# BSPD.net
KiCad netlist of a schematic drawn in Altium Designer
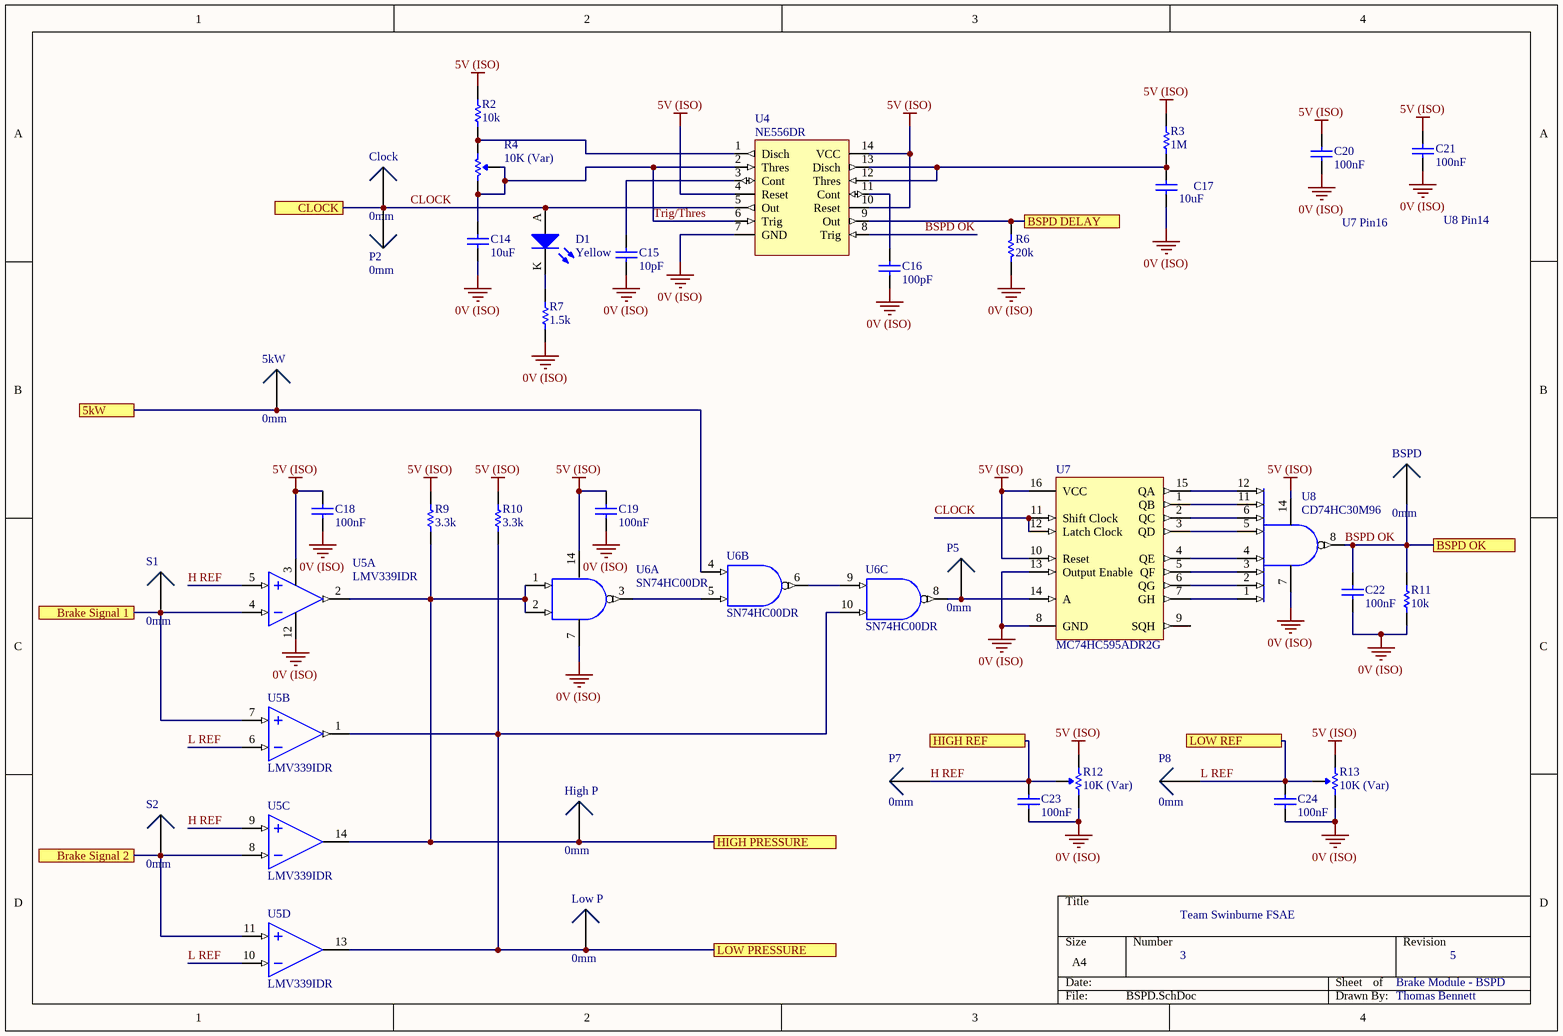
[diagram p0: BSPD.SchDoc]

(export (version "E")
  (design (tool "Eeschema 10.0.6"))
  (components
    (comp (ref "5kW")
      (value "0mm")
      (footprint "SMD Test Point")
      (fields (field (name "PART NUMBER") "SMD Test Point") (field (name "CONTACT") "NA"))
      (libsource (lib "ts_20-standard-connectors") (part "Test Point"))
    )
    (comp (ref "BSPD")
      (value "0mm")
      (footprint "SMD Test Point")
      (fields (field (name "PART NUMBER") "SMD Test Point") (field (name "CONTACT") "NA"))
      (libsource (lib "ts_20-standard-connectors") (part "Test Point"))
    )
    (comp (ref "C14")
      (value "10uF")
      (footprint "0805")
      (fields
        (field (name "PART NUMBER") "GRM21BR6YA106KE43L")
        (field (name "TOLERANCE") "10%")
        (field (name "MANUFACTURER") "muRata")
      )
      (libsource (lib "ts_20-standard-library") (part "Capacitor"))
    )
    (comp (ref "C15")
      (value "10pF")
      (footprint "0805")
      (fields
        (field (name "PART NUMBER") "GRM21A5C2E100JW01D")
        (field (name "TOLERANCE") "±5%")
        (field (name "MANUFACTURER") "muRata")
      )
      (libsource (lib "ts_20-standard-library") (part "Capacitor"))
    )
    (comp (ref "C16")
      (value "100pF")
      (footprint "0805")
      (fields
        (field (name "PART NUMBER") "GCM2165C1H101JA16D")
        (field (name "TOLERANCE") "±5%")
        (field (name "MANUFACTURER") "muRata")
      )
      (libsource (lib "ts_20-standard-library") (part "Capacitor"))
    )
    (comp (ref "C17")
      (value "10uF")
      (footprint "0805")
      (fields
        (field (name "PART NUMBER") "GRM21BR6YA106KE43L")
        (field (name "TOLERANCE") "10%")
        (field (name "MANUFACTURER") "muRata")
      )
      (libsource (lib "ts_20-standard-library") (part "Capacitor"))
    )
    (comp (ref "C18")
      (value "100nF")
      (footprint "0805")
      (fields
        (field (name "PART NUMBER") "GCM21BR71H104KA37L")
        (field (name "TOLERANCE") "±10%")
        (field (name "MANUFACTURER") "muRata")
      )
      (libsource (lib "ts_20-standard-library") (part "Capacitor"))
    )
    (comp (ref "C19")
      (value "100nF")
      (footprint "0805")
      (fields
        (field (name "PART NUMBER") "GCM21BR71E104KA37L")
        (field (name "TOLERANCE") "10%")
        (field (name "MANUFACTURER") "muRata")
      )
      (libsource (lib "ts_20-standard-library") (part "Capacitor"))
    )
    (comp (ref "C20")
      (value "100nF")
      (footprint "0805")
      (fields
        (field (name "PART NUMBER") "GCM21BR71H104KA37L")
        (field (name "TOLERANCE") "±10%")
        (field (name "MANUFACTURER") "muRata")
      )
      (libsource (lib "ts_20-standard-library") (part "Capacitor"))
    )
    (comp (ref "C21")
      (value "100nF")
      (footprint "0805")
      (fields
        (field (name "PART NUMBER") "GCM21BR71H104KA37L")
        (field (name "TOLERANCE") "±10%")
        (field (name "MANUFACTURER") "muRata")
      )
      (libsource (lib "ts_20-standard-library") (part "Capacitor"))
    )
    (comp (ref "C22")
      (value "100nF")
      (footprint "0805")
      (fields
        (field (name "PART NUMBER") "GCM21BR71H104KA37L")
        (field (name "TOLERANCE") "±10%")
        (field (name "MANUFACTURER") "muRata")
      )
      (libsource (lib "ts_20-standard-library") (part "Capacitor"))
    )
    (comp (ref "C23")
      (value "100nF")
      (footprint "0805")
      (fields
        (field (name "PART NUMBER") "GCM21BR71H104KA37L")
        (field (name "TOLERANCE") "±10%")
        (field (name "MANUFACTURER") "muRata")
      )
      (libsource (lib "ts_20-standard-library") (part "Capacitor"))
    )
    (comp (ref "C24")
      (value "100nF")
      (footprint "0805")
      (fields
        (field (name "PART NUMBER") "GCM21BR71H104KA37L")
        (field (name "TOLERANCE") "±10%")
        (field (name "MANUFACTURER") "muRata")
      )
      (libsource (lib "ts_20-standard-library") (part "Capacitor"))
    )
    (comp (ref "Clock")
      (value "0mm")
      (footprint "SMD Test Point")
      (fields (field (name "PART NUMBER") "SMD Test Point") (field (name "CONTACT") "NA"))
      (libsource (lib "ts_20-standard-connectors") (part "Test Point"))
    )
    (comp (ref "D1")
      (value "Yellow")
      (footprint "0805 LED")
      (description "Yellow LED Indication - Discrete 1.75V 0805 (2012 Metric)")
      (fields (field (name "PART NUMBER") "SML-211YTT86") (field (name "MANUFACTURER") "ROHM Semiconductor"))
      (libsource (lib "ts_20-standard-library") (part "LED"))
    )
    (comp (ref "High P")
      (value "0mm")
      (footprint "SMD Test Point")
      (fields (field (name "PART NUMBER") "SMD Test Point") (field (name "CONTACT") "NA"))
      (libsource (lib "ts_20-standard-connectors") (part "Test Point"))
    )
    (comp (ref "Low P")
      (value "0mm")
      (footprint "SMD Test Point")
      (fields (field (name "PART NUMBER") "SMD Test Point") (field (name "CONTACT") "NA"))
      (libsource (lib "ts_20-standard-connectors") (part "Test Point"))
    )
    (comp (ref "P2")
      (value "0mm")
      (footprint "TH Test Point")
      (fields (field (name "PART NUMBER") "TH Test Point") (field (name "CONTACT") "NA"))
      (libsource (lib "ts_20-standard-connectors") (part "Test Point"))
    )
    (comp (ref "P5")
      (value "0mm")
      (footprint "SMD Test Point")
      (fields (field (name "PART NUMBER") "SMD Test Point") (field (name "CONTACT") "NA"))
      (libsource (lib "ts_20-standard-connectors") (part "Test Point"))
    )
    (comp (ref "P7")
      (value "0mm")
      (footprint "TH Test Point")
      (fields (field (name "PART NUMBER") "TH Test Point") (field (name "CONTACT") "NA"))
      (libsource (lib "ts_20-standard-connectors") (part "Test Point"))
    )
    (comp (ref "P8")
      (value "0mm")
      (footprint "TH Test Point")
      (fields (field (name "PART NUMBER") "TH Test Point") (field (name "CONTACT") "NA"))
      (libsource (lib "ts_20-standard-connectors") (part "Test Point"))
    )
    (comp (ref "R2")
      (value "10k")
      (footprint "0805")
      (fields
        (field (name "PART NUMBER") "RC0805FR0710KL")
        (field (name "MANUFACTURER") "YAGEO")
        (field (name "TOLERANCE") "0.01")
      )
      (libsource (lib "ts_20-standard-library") (part "Resistor"))
    )
    (comp (ref "R3")
      (value "1M")
      (footprint "0805")
      (fields
        (field (name "PART NUMBER") "RC0805FR071ML")
        (field (name "MANUFACTURER") "YAGEO")
        (field (name "TOLERANCE") "0.01")
      )
      (libsource (lib "ts_20-standard-library") (part "Resistor"))
    )
    (comp (ref "R4")
      (value "10K (Var)")
      (footprint "B 3296")
      (fields
        (field (name "PART NUMBER") "3296W-1-103LF")
        (field (name "MANUFACTURER") "Bournes Inc")
        (field (name "TOLERANCE") "0.1")
      )
      (libsource (lib "ts_20-standard-library") (part "Resistor (Potentiometer)"))
    )
    (comp (ref "R6")
      (value "20k")
      (footprint "0805")
      (fields
        (field (name "PART NUMBER") "RC0805FR0720KL")
        (field (name "MANUFACTURER") "YAGEO")
        (field (name "TOLERANCE") "0.01")
      )
      (libsource (lib "ts_20-standard-library") (part "Resistor"))
    )
    (comp (ref "R7")
      (value "1.5k")
      (footprint "0805")
      (fields
        (field (name "PART NUMBER") "RC0805FR071K5L")
        (field (name "MANUFACTURER") "YAGEO")
        (field (name "TOLERANCE") "0.01")
      )
      (libsource (lib "ts_20-standard-library") (part "Resistor"))
    )
    (comp (ref "R9")
      (value "3.3k")
      (footprint "0805")
      (fields
        (field (name "PART NUMBER") "RC0805FR073K3L")
        (field (name "MANUFACTURER") "YAGEO")
        (field (name "TOLERANCE") "0.01")
      )
      (libsource (lib "ts_20-standard-library") (part "Resistor"))
    )
    (comp (ref "R10")
      (value "3.3k")
      (footprint "0805")
      (fields
        (field (name "PART NUMBER") "RC0805FR073K3L")
        (field (name "MANUFACTURER") "YAGEO")
        (field (name "TOLERANCE") "0.01")
      )
      (libsource (lib "ts_20-standard-library") (part "Resistor"))
    )
    (comp (ref "R11")
      (value "10k")
      (footprint "0805")
      (fields
        (field (name "PART NUMBER") "RC0805FR0710KL")
        (field (name "MANUFACTURER") "YAGEO")
        (field (name "TOLERANCE") "0.01")
      )
      (libsource (lib "ts_20-standard-library") (part "Resistor"))
    )
    (comp (ref "R12")
      (value "10K (Var)")
      (footprint "B 3296")
      (fields
        (field (name "PART NUMBER") "3296W-1-103LF")
        (field (name "MANUFACTURER") "Bournes Inc")
        (field (name "TOLERANCE") "0.1")
      )
      (libsource (lib "ts_20-standard-library") (part "Resistor (Potentiometer)"))
    )
    (comp (ref "R13")
      (value "10K (Var)")
      (footprint "B 3296")
      (fields
        (field (name "PART NUMBER") "3296W-1-103LF")
        (field (name "MANUFACTURER") "Bournes Inc")
        (field (name "TOLERANCE") "0.1")
      )
      (libsource (lib "ts_20-standard-library") (part "Resistor (Potentiometer)"))
    )
    (comp (ref "S1")
      (value "0mm")
      (footprint "TH Test Point")
      (fields (field (name "PART NUMBER") "TH Test Point") (field (name "CONTACT") "NA"))
      (libsource (lib "ts_20-standard-connectors") (part "Test Point"))
    )
    (comp (ref "S2")
      (value "0mm")
      (footprint "TH Test Point")
      (fields (field (name "PART NUMBER") "TH Test Point") (field (name "CONTACT") "NA"))
      (libsource (lib "ts_20-standard-connectors") (part "Test Point"))
    )
    (comp (ref "U4")
      (value "NE556DR")
      (footprint "14 SOIC")
      (description "IC OSC TIMER DUAL 100KHZ 14SOIC")
      (fields
        (field (name "MANUFACTURER") "Texas Instruments")
        (field (name "DIGIKEY PART NUMBER") "296-26240-1-ND")
      )
      (libsource (lib "ts_20-standard-library") (part "NE556DR"))
    )
    (comp (ref "U5")
      (value "LMV339IDR")
      (footprint "TI 14-SOIC")
      (description "Comparator General Purpose Open Collector 14-SOIC")
      (fields
        (field (name "MANUFACTURER") "Texas Instruments")
        (field (name "DIGIKEY PART NUMBER") "296-6611-2-ND")
      )
      (libsource (lib "ts_20-standard-library") (part "LMV339IDR"))
    )
    (comp (ref "U6")
      (value "SN74HC00DR")
      (footprint "TI 14-SOIC")
      (description "NAND Gate IC 4 Channel 14-SOIC")
      (fields
        (field (name "MANUFACTURER") "Texas Instruments")
        (field (name "DIGIKEY PART NUMBER") "296-1187-2-ND")
      )
      (libsource (lib "ts_20-standard-library") (part "SN74HC00DR"))
    )
    (comp (ref "U7")
      (value "MC74HC595ADR2G")
      (footprint "ON 16-SOIC")
      (description "IC SHIFT REGISTR 8BIT 3ST 16SOIC")
      (fields
        (field (name "MANUFACTURER") "ON Semiconductor")
        (field (name "DIGIKEY PART NUMBER") "MC74HC595ADR2GOSCT-ND")
      )
      (libsource (lib "ts_20-standard-library") (part "MC74HC595ADR2G"))
    )
    (comp (ref "U8")
      (value "CD74HC30M96")
      (footprint "TI 14-SOIC")
      (description "IC GATE NAND 1CH 8-INP 14SOIC")
      (fields
        (field (name "MANUFACTURER") "Texas Instruments")
        (field (name "DIGIKEY PART NUMBER") "296-14521-1-ND")
      )
      (libsource (lib "ts_20-standard-library") (part "CD74HC30M96"))
    )
  )
  (nets
    (net (code "1") (name "/5kW") (class "Default")
      (node (ref "5kW") (pin "1") (pinfunction "1_1") (pintype "passive"))
      (node (ref "U6") (pin "4") (pinfunction "2A_4") (pintype "input"))
    )
    (net (code "2") (name "/BSPD DELAY") (class "Default")
      (node (ref "R6") (pin "1") (pinfunction "1_1") (pintype "passive"))
      (node (ref "U4") (pin "9") (pinfunction "Out_9") (pintype "output"))
    )
    (net (code "3") (name "/BSPD OK") (class "Default")
      (node (ref "BSPD") (pin "1") (pinfunction "1_1") (pintype "passive"))
      (node (ref "C22") (pin "2") (pinfunction "2_2") (pintype "passive"))
      (node (ref "R11") (pin "2") (pinfunction "2_2") (pintype "passive"))
      (node (ref "U4") (pin "8") (pinfunction "Trig_8") (pintype "input"))
      (node (ref "U8") (pin "8") (pinfunction "Output_8") (pintype "output"))
    )
    (net (code "4") (name "/Brake Signal 1") (class "Default")
      (node (ref "S1") (pin "1") (pinfunction "1_1") (pintype "passive"))
      (node (ref "U5") (pin "4") (pinfunction "IN_A-_4") (pintype "input"))
      (node (ref "U5") (pin "7") (pinfunction "IN_B+_7") (pintype "input"))
    )
    (net (code "5") (name "/Brake Signal 2") (class "Default")
      (node (ref "S2") (pin "1") (pinfunction "1_1") (pintype "passive"))
      (node (ref "U5") (pin "11") (pinfunction "IN_D+_11") (pintype "input"))
      (node (ref "U5") (pin "8") (pinfunction "IN_C-_8") (pintype "input"))
    )
    (net (code "6") (name "/CLOCK") (class "Default")
      (node (ref "Clock") (pin "1") (pinfunction "1_1") (pintype "passive"))
      (node (ref "D1") (pin "A") (pinfunction "A_A") (pintype "passive"))
      (node (ref "P2") (pin "1") (pinfunction "1_1") (pintype "passive"))
      (node (ref "U4") (pin "5") (pinfunction "Out_5") (pintype "output"))
      (node (ref "U7") (pin "11") (pinfunction "Shift_Clock_11") (pintype "input"))
      (node (ref "U7") (pin "12") (pinfunction "Latch_Clock_12") (pintype "input"))
    )
    (net (code "7") (name "/H REF") (class "Default")
      (node (ref "C23") (pin "2") (pinfunction "2_2") (pintype "passive"))
      (node (ref "P7") (pin "1") (pinfunction "1_1") (pintype "passive"))
      (node (ref "R12") (pin "2") (pinfunction "Wiper_2") (pintype "passive"))
      (node (ref "U5") (pin "5") (pinfunction "IN_A+_5") (pintype "input"))
      (node (ref "U5") (pin "9") (pinfunction "IN_C+_9") (pintype "input"))
    )
    (net (code "8") (name "/HIGH PRESSURE") (class "Default")
      (node (ref "High P") (pin "1") (pinfunction "1_1") (pintype "passive"))
      (node (ref "R9") (pin "1") (pinfunction "1_1") (pintype "passive"))
      (node (ref "U5") (pin "14") (pinfunction "OUT_C_14") (pintype "passive"))
      (node (ref "U5") (pin "2") (pinfunction "OUT_A_2") (pintype "output"))
      (node (ref "U6") (pin "1") (pinfunction "1A_1") (pintype "input"))
      (node (ref "U6") (pin "2") (pinfunction "1B_2") (pintype "input"))
    )
    (net (code "9") (name "/L REF") (class "Default")
      (node (ref "C24") (pin "2") (pinfunction "2_2") (pintype "passive"))
      (node (ref "P8") (pin "1") (pinfunction "1_1") (pintype "passive"))
      (node (ref "R13") (pin "2") (pinfunction "Wiper_2") (pintype "passive"))
      (node (ref "U5") (pin "10") (pinfunction "IN_D-_10") (pintype "input"))
      (node (ref "U5") (pin "6") (pinfunction "IN_B-_6") (pintype "input"))
    )
    (net (code "10") (name "/LOW PRESSURE") (class "Default")
      (node (ref "Low P") (pin "1") (pinfunction "1_1") (pintype "passive"))
      (node (ref "R10") (pin "1") (pinfunction "1_1") (pintype "passive"))
      (node (ref "U5") (pin "1") (pinfunction "OUT_B_1") (pintype "output"))
      (node (ref "U5") (pin "13") (pinfunction "OUT_D_13") (pintype "passive"))
      (node (ref "U6") (pin "10") (pinfunction "3B_10") (pintype "input"))
    )
    (net (code "11") (name "/Trig{slash}Thres") (class "Default")
      (node (ref "C14") (pin "2") (pinfunction "2_2") (pintype "passive"))
      (node (ref "R4") (pin "1") (pinfunction "CCW_1") (pintype "passive"))
      (node (ref "R4") (pin "2") (pinfunction "Wiper_2") (pintype "passive"))
      (node (ref "U4") (pin "2") (pinfunction "Thres_2") (pintype "input"))
      (node (ref "U4") (pin "6") (pinfunction "Trig_6") (pintype "input"))
    )
    (net (code "12") (name "0V (ISO)") (class "Default")
      (node (ref "C14") (pin "1") (pinfunction "1_1") (pintype "passive"))
      (node (ref "C15") (pin "1") (pinfunction "1_1") (pintype "passive"))
      (node (ref "C16") (pin "1") (pinfunction "1_1") (pintype "passive"))
      (node (ref "C17") (pin "1") (pinfunction "1_1") (pintype "passive"))
      (node (ref "C18") (pin "1") (pinfunction "1_1") (pintype "passive"))
      (node (ref "C19") (pin "1") (pinfunction "1_1") (pintype "passive"))
      (node (ref "C20") (pin "1") (pinfunction "1_1") (pintype "passive"))
      (node (ref "C21") (pin "1") (pinfunction "1_1") (pintype "passive"))
      (node (ref "C22") (pin "1") (pinfunction "1_1") (pintype "passive"))
      (node (ref "C23") (pin "1") (pinfunction "1_1") (pintype "passive"))
      (node (ref "C24") (pin "1") (pinfunction "1_1") (pintype "passive"))
      (node (ref "R11") (pin "1") (pinfunction "1_1") (pintype "passive"))
      (node (ref "R12") (pin "1") (pinfunction "CCW_1") (pintype "passive"))
      (node (ref "R13") (pin "1") (pinfunction "CCW_1") (pintype "passive"))
      (node (ref "R6") (pin "2") (pinfunction "2_2") (pintype "passive"))
      (node (ref "R7") (pin "1") (pinfunction "1_1") (pintype "passive"))
      (node (ref "U4") (pin "7") (pinfunction "GND_7") (pintype "power_in"))
      (node (ref "U5") (pin "12") (pinfunction "V-_12") (pintype "power_in"))
      (node (ref "U6") (pin "7") (pinfunction "GND_7") (pintype "power_in"))
      (node (ref "U7") (pin "13") (pinfunction "Output_Enable_13") (pintype "input"))
      (node (ref "U7") (pin "8") (pinfunction "GND_8") (pintype "power_in"))
      (node (ref "U8") (pin "7") (pinfunction "GND_7") (pintype "power_in"))
    )
    (net (code "13") (name "5V (ISO)") (class "Default")
      (node (ref "C18") (pin "2") (pinfunction "2_2") (pintype "passive"))
      (node (ref "C19") (pin "2") (pinfunction "2_2") (pintype "passive"))
      (node (ref "C20") (pin "2") (pinfunction "2_2") (pintype "passive"))
      (node (ref "C21") (pin "2") (pinfunction "2_2") (pintype "passive"))
      (node (ref "R10") (pin "2") (pinfunction "2_2") (pintype "passive"))
      (node (ref "R12") (pin "3") (pinfunction "CW_3") (pintype "passive"))
      (node (ref "R13") (pin "3") (pinfunction "CW_3") (pintype "passive"))
      (node (ref "R2") (pin "2") (pinfunction "2_2") (pintype "passive"))
      (node (ref "R3") (pin "2") (pinfunction "2_2") (pintype "passive"))
      (node (ref "R9") (pin "2") (pinfunction "2_2") (pintype "passive"))
      (node (ref "U4") (pin "10") (pinfunction "Reset_10") (pintype "passive"))
      (node (ref "U4") (pin "14") (pinfunction "VCC_14") (pintype "passive"))
      (node (ref "U4") (pin "4") (pinfunction "Reset_4") (pintype "passive"))
      (node (ref "U5") (pin "3") (pinfunction "V+_3") (pintype "power_in"))
      (node (ref "U6") (pin "14") (pinfunction "VCC_14") (pintype "power_in"))
      (node (ref "U7") (pin "10") (pinfunction "Reset_10") (pintype "input"))
      (node (ref "U7") (pin "16") (pinfunction "VCC_16") (pintype "power_in"))
      (node (ref "U8") (pin "14") (pinfunction "VCC_14") (pintype "power_in"))
    )
    (net (code "14") (name "Net-(C15-Pad2)") (class "Default")
      (node (ref "C15") (pin "2") (pinfunction "2_2") (pintype "passive"))
      (node (ref "U4") (pin "3") (pinfunction "Cont_3") (pintype "bidirectional"))
    )
    (net (code "15") (name "Net-(C16-Pad2)") (class "Default")
      (node (ref "C16") (pin "2") (pinfunction "2_2") (pintype "passive"))
      (node (ref "U4") (pin "11") (pinfunction "Cont_11") (pintype "bidirectional"))
    )
    (net (code "16") (name "Net-(C17-Pad2)") (class "Default")
      (node (ref "C17") (pin "2") (pinfunction "2_2") (pintype "passive"))
      (node (ref "R3") (pin "1") (pinfunction "1_1") (pintype "passive"))
      (node (ref "U4") (pin "12") (pinfunction "Thres_12") (pintype "input"))
      (node (ref "U4") (pin "13") (pinfunction "Disch_13") (pintype "output"))
    )
    (net (code "17") (name "Net-(D1-PadK)") (class "Default")
      (node (ref "D1") (pin "K") (pinfunction "K_K") (pintype "passive"))
      (node (ref "R7") (pin "2") (pinfunction "2_2") (pintype "passive"))
    )
    (net (code "18") (name "Net-(R4-CW)") (class "Default")
      (node (ref "R2") (pin "1") (pinfunction "1_1") (pintype "passive"))
      (node (ref "R4") (pin "3") (pinfunction "CW_3") (pintype "passive"))
      (node (ref "U4") (pin "1") (pinfunction "Disch_1") (pintype "output"))
    )
    (net (code "19") (name "Net-(U6A-1Y)") (class "Default")
      (node (ref "U6") (pin "3") (pinfunction "1Y_3") (pintype "output"))
      (node (ref "U6") (pin "5") (pinfunction "2B_5") (pintype "input"))
    )
    (net (code "20") (name "Net-(U6B-2Y)") (class "Default")
      (node (ref "U6") (pin "6") (pinfunction "2Y_6") (pintype "output"))
      (node (ref "U6") (pin "9") (pinfunction "3A_9") (pintype "input"))
    )
    (net (code "21") (name "Net-(U6C-3Y)") (class "Default")
      (node (ref "P5") (pin "1") (pinfunction "1_1") (pintype "passive"))
      (node (ref "U6") (pin "8") (pinfunction "3Y_8") (pintype "output"))
      (node (ref "U7") (pin "14") (pinfunction "A_14") (pintype "input"))
    )
    (net (code "22") (name "Net-(U7-GH)") (class "Default")
      (node (ref "U7") (pin "7") (pinfunction "GH_7") (pintype "output"))
      (node (ref "U8") (pin "1") (pinfunction "Input_1") (pintype "input"))
    )
    (net (code "23") (name "Net-(U7-QA)") (class "Default")
      (node (ref "U7") (pin "15") (pinfunction "QA_15") (pintype "output"))
      (node (ref "U8") (pin "12") (pinfunction "Input_12") (pintype "input"))
    )
    (net (code "24") (name "Net-(U7-QB)") (class "Default")
      (node (ref "U7") (pin "1") (pinfunction "QB_1") (pintype "output"))
      (node (ref "U8") (pin "11") (pinfunction "Input_11") (pintype "input"))
    )
    (net (code "25") (name "Net-(U7-QC)") (class "Default")
      (node (ref "U7") (pin "2") (pinfunction "QC_2") (pintype "output"))
      (node (ref "U8") (pin "6") (pinfunction "Input_6") (pintype "input"))
    )
    (net (code "26") (name "Net-(U7-QD)") (class "Default")
      (node (ref "U7") (pin "3") (pinfunction "QD_3") (pintype "output"))
      (node (ref "U8") (pin "5") (pinfunction "Input_5") (pintype "input"))
    )
    (net (code "27") (name "Net-(U7-QE)") (class "Default")
      (node (ref "U7") (pin "4") (pinfunction "QE_4") (pintype "output"))
      (node (ref "U8") (pin "4") (pinfunction "Input_4") (pintype "input"))
    )
    (net (code "28") (name "Net-(U7-QF)") (class "Default")
      (node (ref "U7") (pin "5") (pinfunction "QF_5") (pintype "output"))
      (node (ref "U8") (pin "3") (pinfunction "Input_3") (pintype "input"))
    )
    (net (code "29") (name "Net-(U7-QG)") (class "Default")
      (node (ref "U7") (pin "6") (pinfunction "QG_6") (pintype "output"))
      (node (ref "U8") (pin "2") (pinfunction "Input_2") (pintype "input"))
    )
    (net (code "30") (name "unconnected-(U7-SQH-Pad9)") (class "Default")
      (node (ref "U7") (pin "9") (pinfunction "SQH_9") (pintype "output"))
    )
  )
)
